# 12v_input.net
KiCad netlist of a schematic drawn in Altium Designer
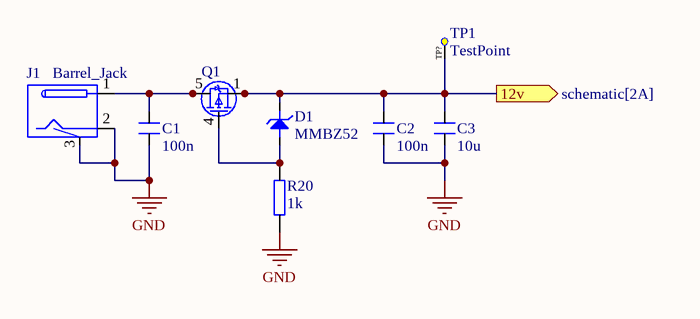
[diagram p0: 12v_input.SchDoc]

(export (version "E")
  (design (tool "Eeschema 10.0.6"))
  (components
    (comp (ref "C1") (value "100n") (footprint "CAP_0805") (libsource (lib "sch_comp") (part "CAP_0805")))
    (comp (ref "C2") (value "100n") (footprint "CAP_0805") (libsource (lib "sch_comp") (part "CAP_0805")))
    (comp (ref "C3") (value "10u") (footprint "CAP_0805") (libsource (lib "sch_comp") (part "CAP_0805")))
    (comp (ref "D1") (value "MMBZ52") (footprint "MMBZ52") (libsource (lib "sch_comp") (part "MMBZ52")))
    (comp (ref "J1")
      (value "Barrel_Jack")
      (footprint "power jack")
      (libsource (lib "sch_comp") (part "Barrel_Jack"))
    )
    (comp (ref "Q1") (value "Q1") (footprint "DMP3036SFV7") (libsource (lib "sch_comp") (part "Q1")))
    (comp (ref "R20") (value "1k") (footprint "RES0402") (libsource (lib "sch_comp") (part "RES 0402")))
    (comp (ref "TP1")
      (value "TestPoint")
      (footprint "Test_point")
      (libsource (lib "sch_comp") (part "test_point"))
    )
  )
  (nets
    (net (code "1") (name "/12v") (class "Default")
      (node (ref "C2") (pin "2") (pintype "passive"))
      (node (ref "C3") (pin "2") (pintype "passive"))
      (node (ref "D1") (pin "3") (pinfunction "Cathode_3") (pintype "passive"))
      (node (ref "Q1") (pin "1") (pinfunction "1_1") (pintype "passive"))
      (node (ref "Q1") (pin "2") (pinfunction "2_2") (pintype "passive"))
      (node (ref "Q1") (pin "3") (pinfunction "3_3") (pintype "passive"))
      (node (ref "TP1") (pin "TP?") (pinfunction "Test_Point_TP?") (pintype "passive"))
    )
    (net (code "2") (name "GND") (class "Default")
      (node (ref "C1") (pin "1") (pintype "passive"))
      (node (ref "C2") (pin "1") (pintype "passive"))
      (node (ref "C3") (pin "1") (pintype "passive"))
      (node (ref "J1") (pin "2") (pinfunction "10_2") (pintype "passive"))
      (node (ref "J1") (pin "3") (pinfunction "3_3") (pintype "passive"))
      (node (ref "R20") (pin "1") (pintype "passive"))
    )
    (net (code "3") (name "Net-(C1-Pad2)") (class "Default")
      (node (ref "C1") (pin "2") (pintype "passive"))
      (node (ref "J1") (pin "1") (pintype "passive"))
      (node (ref "Q1") (pin "5") (pinfunction "5_5") (pintype "passive"))
      (node (ref "Q1") (pin "6") (pinfunction "6_6") (pintype "passive"))
      (node (ref "Q1") (pin "7") (pinfunction "7_7") (pintype "passive"))
      (node (ref "Q1") (pin "8") (pinfunction "8_8") (pintype "passive"))
      (node (ref "Q1") (pin "9") (pinfunction "9_9") (pintype "passive"))
    )
    (net (code "4") (name "Net-(D1-Anode)") (class "Default")
      (node (ref "D1") (pin "1") (pinfunction "Anode_1") (pintype "passive"))
      (node (ref "Q1") (pin "4") (pinfunction "4_4") (pintype "passive"))
      (node (ref "R20") (pin "2") (pintype "passive"))
    )
  )
)
